# IOB-generic.net
KiCad netlist of a schematic drawn in EAGLE
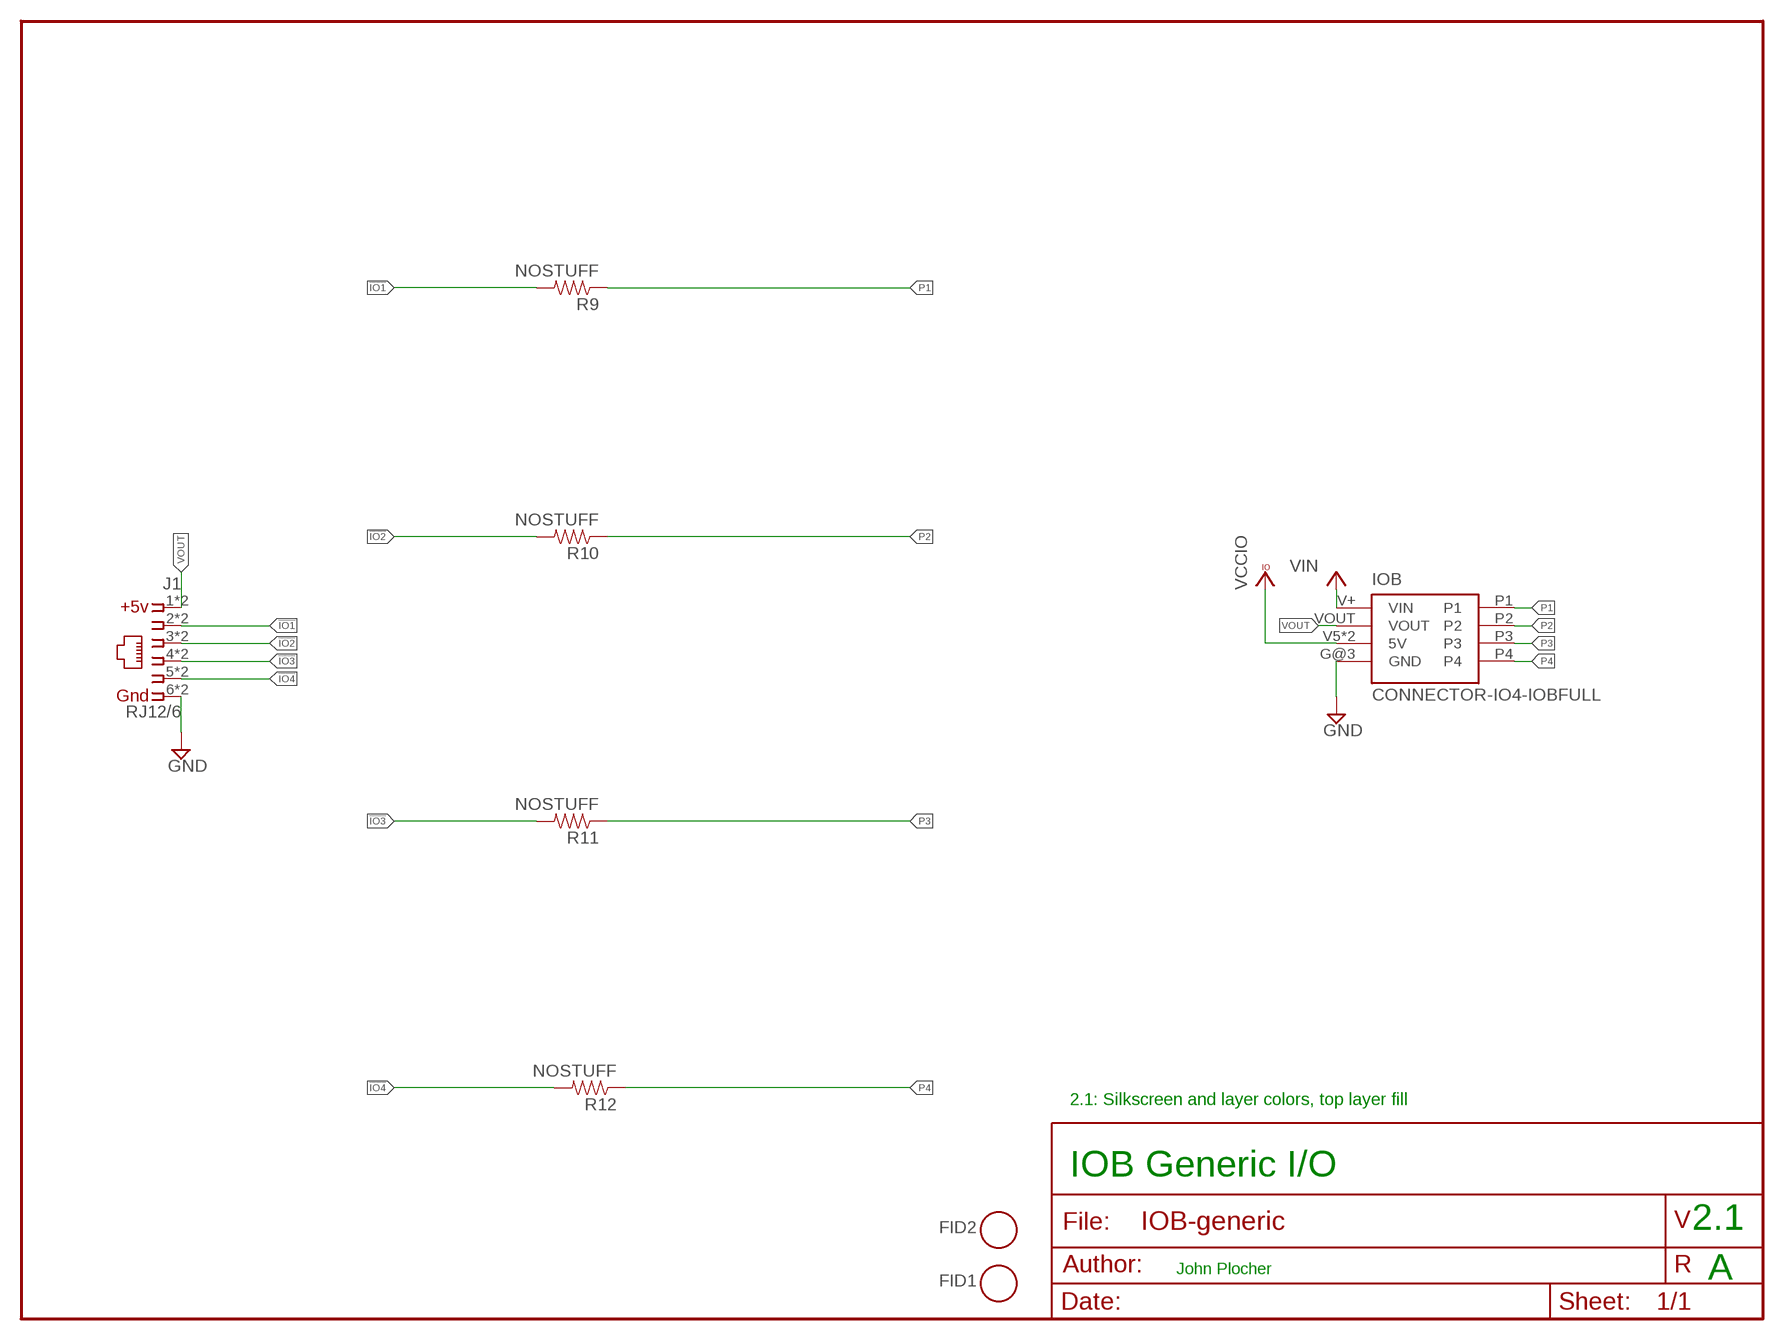
[diagram p0: schematic, sheet 1]

(export (version "E")
  (design (tool "Eeschema 10.0.6"))
  (components
    (comp (ref "FID1")
      (value "FIDUCIAL")
      (footprint "eagle-import:FIDUCIAL_1MM")
      (libsource (lib "eagle-import") (part "FIDUCIAL"))
    )
    (comp (ref "FID2")
      (value "FIDUCIAL")
      (footprint "eagle-import:FIDUCIAL_1MM")
      (libsource (lib "eagle-import") (part "FIDUCIAL"))
    )
    (comp (ref "IOB")
      (value "CONNECTOR-IO4-IOBFULL")
      (footprint "eagle-import:IO4-IOB")
      (libsource (lib "eagle-import") (part "CONNECTOR-IO4-IOBFULL"))
    )
    (comp (ref "J1")
      (value "RJ12/6")
      (footprint "eagle-import:RJ24-INVERTED-PINS")
      (libsource (lib "eagle-import") (part "CONNECTOR-IO4IPINS"))
    )
    (comp (ref "R9")
      (value "NOSTUFF")
      (footprint "eagle-import:AXIAL-0.4-RES")
      (libsource (lib "eagle-import") (part "RPTH04"))
    )
    (comp (ref "R10")
      (value "NOSTUFF")
      (footprint "eagle-import:AXIAL-0.4-RES")
      (libsource (lib "eagle-import") (part "RPTH04"))
    )
    (comp (ref "R11")
      (value "NOSTUFF")
      (footprint "eagle-import:AXIAL-0.4-RES")
      (libsource (lib "eagle-import") (part "RPTH04"))
    )
    (comp (ref "R12")
      (value "NOSTUFF")
      (footprint "eagle-import:AXIAL-0.4-RES")
      (libsource (lib "eagle-import") (part "RPTH04"))
    )
  )
  (nets
    (net (code "1") (name "/~{IO1}") (class "Default")
      (node (ref "J1") (pin "2") (pinfunction "2_2") (pintype "passive"))
      (node (ref "J1") (pin "2@1") (pinfunction "2_2@1") (pintype "passive"))
      (node (ref "R9") (pin "P$2") (pinfunction "2_P$2") (pintype "passive"))
    )
    (net (code "2") (name "/~{IO2}") (class "Default")
      (node (ref "J1") (pin "3") (pinfunction "3_3") (pintype "passive"))
      (node (ref "J1") (pin "3@1") (pinfunction "3_3@1") (pintype "passive"))
      (node (ref "R10") (pin "P$2") (pinfunction "2_P$2") (pintype "passive"))
    )
    (net (code "3") (name "/~{IO3}") (class "Default")
      (node (ref "J1") (pin "4") (pinfunction "4_4") (pintype "passive"))
      (node (ref "J1") (pin "4@1") (pinfunction "4_4@1") (pintype "passive"))
      (node (ref "R11") (pin "P$2") (pinfunction "2_P$2") (pintype "passive"))
    )
    (net (code "4") (name "/~{IO4}") (class "Default")
      (node (ref "J1") (pin "5") (pinfunction "5_5") (pintype "passive"))
      (node (ref "J1") (pin "5@1") (pinfunction "5_5@1") (pintype "passive"))
      (node (ref "R12") (pin "P$2") (pinfunction "2_P$2") (pintype "passive"))
    )
    (net (code "5") (name "GND") (class "Default")
      (node (ref "IOB") (pin "G@3") (pinfunction "GND_G@3") (pintype "power_in"))
      (node (ref "J1") (pin "6") (pinfunction "6_6") (pintype "power_in"))
      (node (ref "J1") (pin "6@1") (pinfunction "6_6@1") (pintype "power_in"))
    )
    (net (code "6") (name "P1") (class "Default")
      (node (ref "IOB") (pin "P1") (pinfunction "P1_P1") (pintype "bidirectional"))
      (node (ref "R9") (pin "P$1") (pinfunction "1_P$1") (pintype "passive"))
    )
    (net (code "7") (name "P2") (class "Default")
      (node (ref "IOB") (pin "P2") (pinfunction "P2_P2") (pintype "bidirectional"))
      (node (ref "R10") (pin "P$1") (pinfunction "1_P$1") (pintype "passive"))
    )
    (net (code "8") (name "P3") (class "Default")
      (node (ref "IOB") (pin "P3") (pinfunction "P3_P3") (pintype "bidirectional"))
      (node (ref "R11") (pin "P$1") (pinfunction "1_P$1") (pintype "passive"))
    )
    (net (code "9") (name "P4") (class "Default")
      (node (ref "IOB") (pin "P4") (pinfunction "P4_P4") (pintype "bidirectional"))
      (node (ref "R12") (pin "P$1") (pinfunction "1_P$1") (pintype "passive"))
    )
    (net (code "10") (name "VCCIO") (class "Default")
      (node (ref "IOB") (pin "V5") (pinfunction "5V_V5") (pintype "power_in"))
      (node (ref "IOB") (pin "V5@1") (pinfunction "5V_V5@1") (pintype "power_in"))
    )
    (net (code "11") (name "VIN") (class "Default")
      (node (ref "IOB") (pin "V+") (pinfunction "VIN_V+") (pintype "power_in"))
    )
    (net (code "12") (name "VOUT") (class "Default")
      (node (ref "IOB") (pin "VOUT") (pinfunction "VOUT_VOUT") (pintype "power_in"))
      (node (ref "J1") (pin "1") (pinfunction "1_1") (pintype "power_in"))
      (node (ref "J1") (pin "1@1") (pinfunction "1_1@1") (pintype "power_in"))
    )
  )
)
